# BlinkyTile_controller.net
KiCad netlist of a schematic drawn in EAGLE
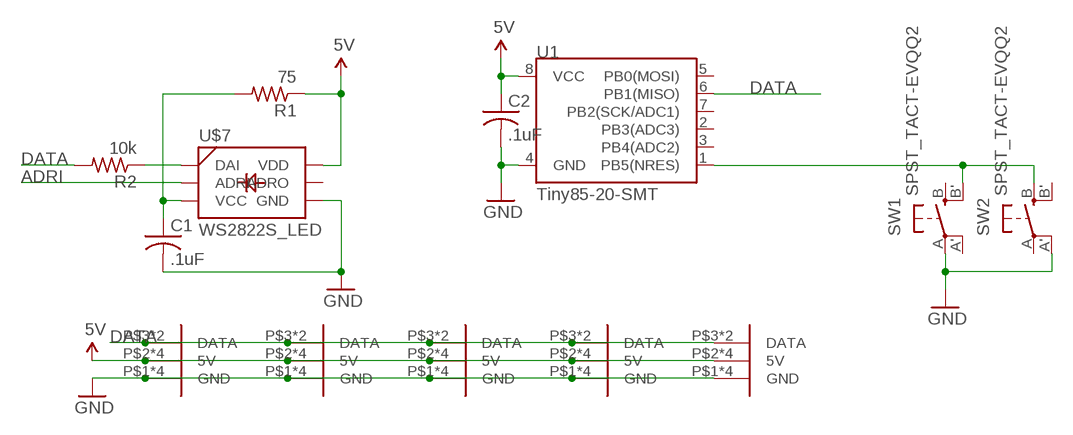
[diagram p0: schematic, sheet 1]

(export (version "E")
  (design (tool "Eeschema 10.0.6"))
  (components
    (comp (ref "C1")
      (value ".1uF")
      (footprint "eagle-import:C0603")
      (libsource (lib "eagle-import") (part "C-USC0603"))
    )
    (comp (ref "C2")
      (value ".1uF")
      (footprint "eagle-import:C0603")
      (libsource (lib "eagle-import") (part "C-USC0603"))
    )
    (comp (ref "R1")
      (value "75")
      (footprint "eagle-import:R0603")
      (libsource (lib "eagle-import") (part "R-US_R0603"))
    )
    (comp (ref "R2")
      (value "10k")
      (footprint "eagle-import:R0603")
      (libsource (lib "eagle-import") (part "R-US_R0603"))
    )
    (comp (ref "SW1")
      (value "SPST_TACT-EVQQ2")
      (footprint "eagle-import:EVQ-Q2")
      (libsource (lib "eagle-import") (part "SPST_TACT-EVQQ2"))
    )
    (comp (ref "SW2")
      (value "SPST_TACT-EVQQ2")
      (footprint "eagle-import:EVQ-Q2")
      (libsource (lib "eagle-import") (part "SPST_TACT-EVQQ2"))
    )
    (comp (ref "U$2")
      (value "D_EDGESLOT")
      (footprint "eagle-import:D_EDGE_SLOT")
      (libsource (lib "eagle-import") (part "D_EDGESLOT"))
    )
    (comp (ref "U$3")
      (value "D_EDGESLOT")
      (footprint "eagle-import:D_EDGE_SLOT")
      (libsource (lib "eagle-import") (part "D_EDGESLOT"))
    )
    (comp (ref "U$4")
      (value "D_EDGESLOT")
      (footprint "eagle-import:D_EDGE_SLOT")
      (libsource (lib "eagle-import") (part "D_EDGESLOT"))
    )
    (comp (ref "U$5")
      (value "D_EDGESLOT")
      (footprint "eagle-import:D_EDGE_SLOT")
      (libsource (lib "eagle-import") (part "D_EDGESLOT"))
    )
    (comp (ref "U$6")
      (value "D_EDGESLOT")
      (footprint "eagle-import:D_EDGE_SLOT")
      (libsource (lib "eagle-import") (part "D_EDGESLOT"))
    )
    (comp (ref "U$7")
      (value "WS2822S_LED")
      (footprint "eagle-import:WS2822S_LED")
      (libsource (lib "eagle-import") (part "WS2822S_LED"))
    )
    (comp (ref "U1")
      (value "Tiny85-20-SMT")
      (footprint "eagle-import:SO08-EIAJ")
      (libsource (lib "eagle-import") (part "ATTINY45TINY85-20-SMT"))
    )
  )
  (nets
    (net (code "1") (name "/ADRI") (class "Default")
      (node (ref "U$7") (pin "2") (pinfunction "ADRI_2") (pintype "input"))
    )
    (net (code "2") (name "/DATA") (class "Default")
      (node (ref "R2") (pin "2") (pinfunction "2_2") (pintype "passive"))
      (node (ref "U$2") (pin "P$3") (pinfunction "DATA_P$3") (pintype "bidirectional"))
      (node (ref "U$2") (pin "P$8") (pinfunction "DATA_P$8") (pintype "bidirectional"))
      (node (ref "U$3") (pin "P$3") (pinfunction "DATA_P$3") (pintype "bidirectional"))
      (node (ref "U$3") (pin "P$8") (pinfunction "DATA_P$8") (pintype "bidirectional"))
      (node (ref "U$4") (pin "P$3") (pinfunction "DATA_P$3") (pintype "bidirectional"))
      (node (ref "U$4") (pin "P$8") (pinfunction "DATA_P$8") (pintype "bidirectional"))
      (node (ref "U$5") (pin "P$3") (pinfunction "DATA_P$3") (pintype "bidirectional"))
      (node (ref "U$5") (pin "P$8") (pinfunction "DATA_P$8") (pintype "bidirectional"))
      (node (ref "U$6") (pin "P$3") (pinfunction "DATA_P$3") (pintype "bidirectional"))
      (node (ref "U$6") (pin "P$8") (pinfunction "DATA_P$8") (pintype "bidirectional"))
      (node (ref "U1") (pin "6") (pinfunction "PB1(MISO)_6") (pintype "bidirectional"))
    )
    (net (code "3") (name "5V") (class "Default")
      (node (ref "C2") (pin "1") (pinfunction "1_1") (pintype "passive"))
      (node (ref "R1") (pin "1") (pinfunction "1_1") (pintype "passive"))
      (node (ref "U$2") (pin "P$2") (pinfunction "5V_P$2") (pintype "bidirectional"))
      (node (ref "U$2") (pin "P$4") (pinfunction "5V_P$4") (pintype "bidirectional"))
      (node (ref "U$2") (pin "P$7") (pinfunction "5V_P$7") (pintype "bidirectional"))
      (node (ref "U$2") (pin "P$9") (pinfunction "5V_P$9") (pintype "bidirectional"))
      (node (ref "U$3") (pin "P$2") (pinfunction "5V_P$2") (pintype "bidirectional"))
      (node (ref "U$3") (pin "P$4") (pinfunction "5V_P$4") (pintype "bidirectional"))
      (node (ref "U$3") (pin "P$7") (pinfunction "5V_P$7") (pintype "bidirectional"))
      (node (ref "U$3") (pin "P$9") (pinfunction "5V_P$9") (pintype "bidirectional"))
      (node (ref "U$4") (pin "P$2") (pinfunction "5V_P$2") (pintype "bidirectional"))
      (node (ref "U$4") (pin "P$4") (pinfunction "5V_P$4") (pintype "bidirectional"))
      (node (ref "U$4") (pin "P$7") (pinfunction "5V_P$7") (pintype "bidirectional"))
      (node (ref "U$4") (pin "P$9") (pinfunction "5V_P$9") (pintype "bidirectional"))
      (node (ref "U$5") (pin "P$2") (pinfunction "5V_P$2") (pintype "bidirectional"))
      (node (ref "U$5") (pin "P$4") (pinfunction "5V_P$4") (pintype "bidirectional"))
      (node (ref "U$5") (pin "P$7") (pinfunction "5V_P$7") (pintype "bidirectional"))
      (node (ref "U$5") (pin "P$9") (pinfunction "5V_P$9") (pintype "bidirectional"))
      (node (ref "U$6") (pin "P$2") (pinfunction "5V_P$2") (pintype "bidirectional"))
      (node (ref "U$6") (pin "P$4") (pinfunction "5V_P$4") (pintype "bidirectional"))
      (node (ref "U$6") (pin "P$7") (pinfunction "5V_P$7") (pintype "bidirectional"))
      (node (ref "U$6") (pin "P$9") (pinfunction "5V_P$9") (pintype "bidirectional"))
      (node (ref "U$7") (pin "6") (pinfunction "VDD_6") (pintype "power_in"))
      (node (ref "U1") (pin "8") (pinfunction "VCC_8") (pintype "bidirectional"))
    )
    (net (code "4") (name "GND") (class "Default")
      (node (ref "C1") (pin "2") (pinfunction "2_2") (pintype "passive"))
      (node (ref "C2") (pin "2") (pinfunction "2_2") (pintype "passive"))
      (node (ref "SW1") (pin "A") (pinfunction "P_A") (pintype "passive"))
      (node (ref "SW2") (pin "A'") (pinfunction "P1_A'") (pintype "passive"))
      (node (ref "U$2") (pin "P$1") (pinfunction "GND_P$1") (pintype "bidirectional"))
      (node (ref "U$2") (pin "P$10") (pinfunction "GND_P$10") (pintype "bidirectional"))
      (node (ref "U$2") (pin "P$5") (pinfunction "GND_P$5") (pintype "bidirectional"))
      (node (ref "U$2") (pin "P$6") (pinfunction "GND_P$6") (pintype "bidirectional"))
      (node (ref "U$3") (pin "P$1") (pinfunction "GND_P$1") (pintype "bidirectional"))
      (node (ref "U$3") (pin "P$10") (pinfunction "GND_P$10") (pintype "bidirectional"))
      (node (ref "U$3") (pin "P$5") (pinfunction "GND_P$5") (pintype "bidirectional"))
      (node (ref "U$3") (pin "P$6") (pinfunction "GND_P$6") (pintype "bidirectional"))
      (node (ref "U$4") (pin "P$1") (pinfunction "GND_P$1") (pintype "bidirectional"))
      (node (ref "U$4") (pin "P$10") (pinfunction "GND_P$10") (pintype "bidirectional"))
      (node (ref "U$4") (pin "P$5") (pinfunction "GND_P$5") (pintype "bidirectional"))
      (node (ref "U$4") (pin "P$6") (pinfunction "GND_P$6") (pintype "bidirectional"))
      (node (ref "U$5") (pin "P$1") (pinfunction "GND_P$1") (pintype "bidirectional"))
      (node (ref "U$5") (pin "P$10") (pinfunction "GND_P$10") (pintype "bidirectional"))
      (node (ref "U$5") (pin "P$5") (pinfunction "GND_P$5") (pintype "bidirectional"))
      (node (ref "U$5") (pin "P$6") (pinfunction "GND_P$6") (pintype "bidirectional"))
      (node (ref "U$6") (pin "P$1") (pinfunction "GND_P$1") (pintype "bidirectional"))
      (node (ref "U$6") (pin "P$10") (pinfunction "GND_P$10") (pintype "bidirectional"))
      (node (ref "U$6") (pin "P$5") (pinfunction "GND_P$5") (pintype "bidirectional"))
      (node (ref "U$6") (pin "P$6") (pinfunction "GND_P$6") (pintype "bidirectional"))
      (node (ref "U$7") (pin "4") (pinfunction "GND_4") (pintype "power_in"))
      (node (ref "U1") (pin "4") (pinfunction "GND_4") (pintype "bidirectional"))
    )
    (net (code "5") (name "Net-(SW1-S1)") (class "Default")
      (node (ref "SW1") (pin "B'") (pinfunction "S1_B'") (pintype "passive"))
      (node (ref "SW2") (pin "B") (pinfunction "S_B") (pintype "passive"))
      (node (ref "U1") (pin "1") (pinfunction "PB5(NRES)_1") (pintype "bidirectional"))
    )
    (net (code "6") (name "Net-(U$7-DAI)") (class "Default")
      (node (ref "R2") (pin "1") (pinfunction "1_1") (pintype "passive"))
      (node (ref "U$7") (pin "1") (pinfunction "DAI_1") (pintype "input"))
    )
    (net (code "7") (name "Net-(U$7-VCC)") (class "Default")
      (node (ref "C1") (pin "1") (pinfunction "1_1") (pintype "passive"))
      (node (ref "R1") (pin "2") (pinfunction "2_2") (pintype "passive"))
      (node (ref "U$7") (pin "3") (pinfunction "VCC_3") (pintype "power_in"))
    )
    (net (code "8") (name "unconnected-(SW1-P1-PadA')") (class "Default")
      (node (ref "SW1") (pin "A'") (pinfunction "P1_A'") (pintype "passive"))
    )
    (net (code "9") (name "unconnected-(SW1-S-PadB)") (class "Default")
      (node (ref "SW1") (pin "B") (pinfunction "S_B") (pintype "passive"))
    )
    (net (code "10") (name "unconnected-(SW2-P-PadA)") (class "Default")
      (node (ref "SW2") (pin "A") (pinfunction "P_A") (pintype "passive"))
    )
    (net (code "11") (name "unconnected-(SW2-S1-PadB')") (class "Default")
      (node (ref "SW2") (pin "B'") (pinfunction "S1_B'") (pintype "passive"))
    )
    (net (code "12") (name "unconnected-(U$7-ADRO-Pad5)") (class "Default")
      (node (ref "U$7") (pin "5") (pinfunction "ADRO_5") (pintype "output"))
    )
    (net (code "13") (name "unconnected-(U1-PB0(MOSI)-Pad5)") (class "Default")
      (node (ref "U1") (pin "5") (pinfunction "PB0(MOSI)_5") (pintype "bidirectional"))
    )
    (net (code "14") (name "unconnected-(U1-PB2(SCK{slash}ADC1)-Pad7)") (class "Default")
      (node (ref "U1") (pin "7") (pinfunction "PB2(SCK/ADC1)_7") (pintype "bidirectional"))
    )
    (net (code "15") (name "unconnected-(U1-PB3(ADC3)-Pad2)") (class "Default")
      (node (ref "U1") (pin "2") (pinfunction "PB3(ADC3)_2") (pintype "bidirectional"))
    )
    (net (code "16") (name "unconnected-(U1-PB4(ADC2)-Pad3)") (class "Default")
      (node (ref "U1") (pin "3") (pinfunction "PB4(ADC2)_3") (pintype "bidirectional"))
    )
  )
)
